# base_schematic.net
KiCad netlist of a schematic drawn in Altium Designer
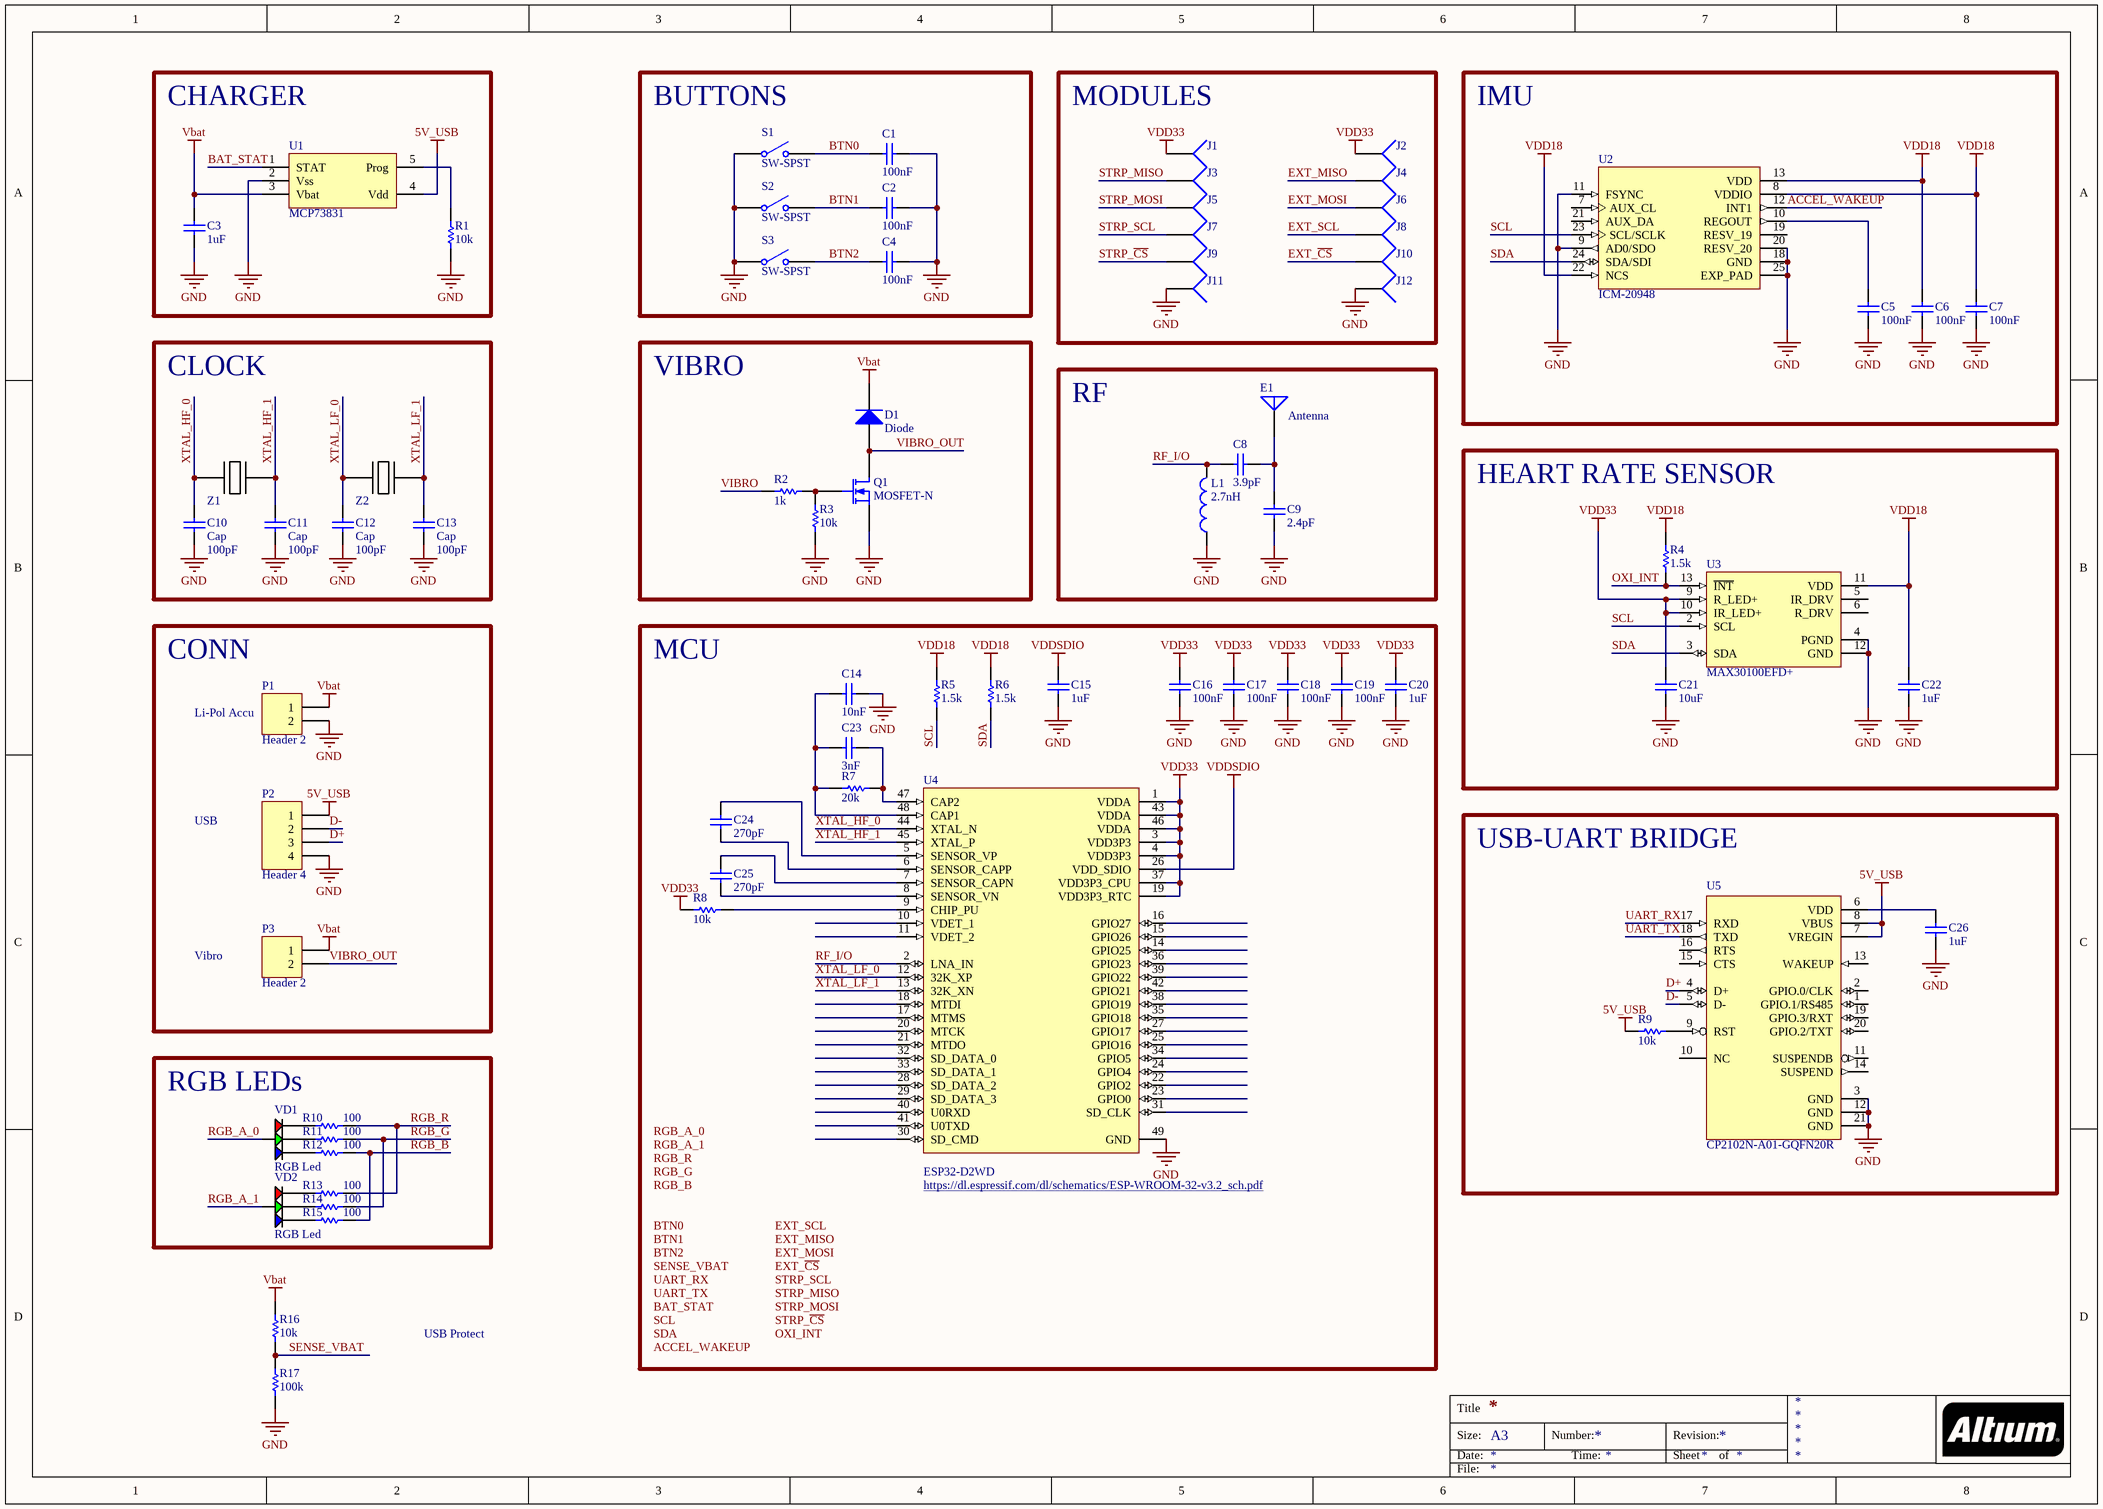
[diagram p0: base_schematic.SchDoc]

(export (version "E")
  (design (tool "Eeschema 10.0.6"))
  (components
    (comp (ref "C1")
      (value "100nF")
      (footprint "RAD-0.3")
      (description "Capacitor")
      (fields (field (name "PUBLISHER") "Altium Limited"))
      (libsource (lib "Miscellaneous Devices") (part "Cap"))
    )
    (comp (ref "C2")
      (value "100nF")
      (footprint "RAD-0.3")
      (description "Capacitor")
      (fields (field (name "PUBLISHER") "Altium Limited"))
      (libsource (lib "Miscellaneous Devices") (part "Cap"))
    )
    (comp (ref "C3")
      (value "1uF")
      (footprint "RAD-0.3")
      (description "Capacitor")
      (fields (field (name "PUBLISHER") "Altium Limited"))
      (libsource (lib "Miscellaneous Devices") (part "Cap"))
    )
    (comp (ref "C4")
      (value "100nF")
      (footprint "RAD-0.3")
      (description "Capacitor")
      (fields (field (name "PUBLISHER") "Altium Limited"))
      (libsource (lib "Miscellaneous Devices") (part "Cap"))
    )
    (comp (ref "C5")
      (value "100nF")
      (footprint "RAD-0.3")
      (description "Capacitor")
      (fields (field (name "PUBLISHER") "Altium Limited"))
      (libsource (lib "Miscellaneous Devices") (part "Cap"))
    )
    (comp (ref "C6")
      (value "100nF")
      (footprint "RAD-0.3")
      (description "Capacitor")
      (fields (field (name "PUBLISHER") "Altium Limited"))
      (libsource (lib "Miscellaneous Devices") (part "Cap"))
    )
    (comp (ref "C7")
      (value "100nF")
      (footprint "RAD-0.3")
      (description "Capacitor")
      (fields (field (name "PUBLISHER") "Altium Limited"))
      (libsource (lib "Miscellaneous Devices") (part "Cap"))
    )
    (comp (ref "C8")
      (value "3.9pF")
      (footprint "RAD-0.3")
      (description "Capacitor")
      (fields (field (name "PUBLISHER") "Altium Limited"))
      (libsource (lib "Miscellaneous Devices") (part "Cap"))
    )
    (comp (ref "C9")
      (value "2.4pF")
      (footprint "RAD-0.3")
      (description "Capacitor")
      (fields (field (name "PUBLISHER") "Altium Limited"))
      (libsource (lib "Miscellaneous Devices") (part "Cap"))
    )
    (comp (ref "C10")
      (value "Cap")
      (footprint "RAD-0.3")
      (description "Capacitor")
      (fields (field (name "ALTIUM_VALUE") "100pF") (field (name "PUBLISHER") "Altium Limited"))
      (libsource (lib "Miscellaneous Devices") (part "Cap"))
    )
    (comp (ref "C11")
      (value "Cap")
      (footprint "RAD-0.3")
      (description "Capacitor")
      (fields (field (name "ALTIUM_VALUE") "100pF") (field (name "PUBLISHER") "Altium Limited"))
      (libsource (lib "Miscellaneous Devices") (part "Cap"))
    )
    (comp (ref "C12")
      (value "Cap")
      (footprint "RAD-0.3")
      (description "Capacitor")
      (fields (field (name "ALTIUM_VALUE") "100pF") (field (name "PUBLISHER") "Altium Limited"))
      (libsource (lib "Miscellaneous Devices") (part "Cap"))
    )
    (comp (ref "C13")
      (value "Cap")
      (footprint "RAD-0.3")
      (description "Capacitor")
      (fields (field (name "ALTIUM_VALUE") "100pF") (field (name "PUBLISHER") "Altium Limited"))
      (libsource (lib "Miscellaneous Devices") (part "Cap"))
    )
    (comp (ref "C14")
      (value "10nF")
      (footprint "RAD-0.3")
      (description "Capacitor")
      (fields (field (name "PUBLISHER") "Altium Limited"))
      (libsource (lib "Miscellaneous Devices") (part "Cap"))
    )
    (comp (ref "C15")
      (value "1uF")
      (footprint "RAD-0.3")
      (description "Capacitor")
      (fields (field (name "PUBLISHER") "Altium Limited"))
      (libsource (lib "Miscellaneous Devices") (part "Cap"))
    )
    (comp (ref "C16")
      (value "100nF")
      (footprint "RAD-0.3")
      (description "Capacitor")
      (fields (field (name "PUBLISHER") "Altium Limited"))
      (libsource (lib "Miscellaneous Devices") (part "Cap"))
    )
    (comp (ref "C17")
      (value "100nF")
      (footprint "RAD-0.3")
      (description "Capacitor")
      (fields (field (name "PUBLISHER") "Altium Limited"))
      (libsource (lib "Miscellaneous Devices") (part "Cap"))
    )
    (comp (ref "C18")
      (value "100nF")
      (footprint "RAD-0.3")
      (description "Capacitor")
      (fields (field (name "PUBLISHER") "Altium Limited"))
      (libsource (lib "Miscellaneous Devices") (part "Cap"))
    )
    (comp (ref "C19")
      (value "100nF")
      (footprint "RAD-0.3")
      (description "Capacitor")
      (fields (field (name "PUBLISHER") "Altium Limited"))
      (libsource (lib "Miscellaneous Devices") (part "Cap"))
    )
    (comp (ref "C20")
      (value "1uF")
      (footprint "RAD-0.3")
      (description "Capacitor")
      (fields (field (name "PUBLISHER") "Altium Limited"))
      (libsource (lib "Miscellaneous Devices") (part "Cap"))
    )
    (comp (ref "C21")
      (value "10uF")
      (footprint "RAD-0.3")
      (description "Capacitor")
      (fields (field (name "PUBLISHER") "Altium Limited"))
      (libsource (lib "Miscellaneous Devices") (part "Cap"))
    )
    (comp (ref "C22")
      (value "1uF")
      (footprint "RAD-0.3")
      (description "Capacitor")
      (fields (field (name "PUBLISHER") "Altium Limited"))
      (libsource (lib "Miscellaneous Devices") (part "Cap"))
    )
    (comp (ref "C23")
      (value "3nF")
      (footprint "RAD-0.3")
      (description "Capacitor")
      (fields (field (name "PUBLISHER") "Altium Limited"))
      (libsource (lib "Miscellaneous Devices") (part "Cap"))
    )
    (comp (ref "C24")
      (value "270pF")
      (footprint "RAD-0.3")
      (description "Capacitor")
      (fields (field (name "PUBLISHER") "Altium Limited"))
      (libsource (lib "Miscellaneous Devices") (part "Cap"))
    )
    (comp (ref "C25")
      (value "270pF")
      (footprint "RAD-0.3")
      (description "Capacitor")
      (fields (field (name "PUBLISHER") "Altium Limited"))
      (libsource (lib "Miscellaneous Devices") (part "Cap"))
    )
    (comp (ref "C26")
      (value "1uF")
      (footprint "RAD-0.3")
      (description "Capacitor")
      (fields (field (name "PUBLISHER") "Altium Limited"))
      (libsource (lib "Miscellaneous Devices") (part "Cap"))
    )
    (comp (ref "D1")
      (value "Diode")
      (footprint "SMC")
      (description "Default Diode")
      (fields (field (name "PUBLISHER") "Altium Limited"))
      (libsource (lib "Miscellaneous Devices") (part "Diode"))
    )
    (comp (ref "E1")
      (value "Antenna")
      (footprint "PIN1")
      (description "Generic Antenna")
      (fields (field (name "PUBLISHER") "Altium Limited"))
      (libsource (lib "Miscellaneous Devices") (part "Antenna"))
    )
    (comp (ref "J1")
      (value "Socket")
      (footprint "PIN1")
      (fields (field (name "PUBLISHER") "Altium Limited"))
      (libsource (lib "Miscellaneous Connectors") (part "Socket"))
    )
    (comp (ref "J2")
      (value "Socket")
      (footprint "PIN1")
      (fields (field (name "PUBLISHER") "Altium Limited"))
      (libsource (lib "Miscellaneous Connectors") (part "Socket"))
    )
    (comp (ref "J3")
      (value "Socket")
      (footprint "PIN1")
      (fields (field (name "PUBLISHER") "Altium Limited"))
      (libsource (lib "Miscellaneous Connectors") (part "Socket"))
    )
    (comp (ref "J4")
      (value "Socket")
      (footprint "PIN1")
      (fields (field (name "PUBLISHER") "Altium Limited"))
      (libsource (lib "Miscellaneous Connectors") (part "Socket"))
    )
    (comp (ref "J5")
      (value "Socket")
      (footprint "PIN1")
      (fields (field (name "PUBLISHER") "Altium Limited"))
      (libsource (lib "Miscellaneous Connectors") (part "Socket"))
    )
    (comp (ref "J6")
      (value "Socket")
      (footprint "PIN1")
      (fields (field (name "PUBLISHER") "Altium Limited"))
      (libsource (lib "Miscellaneous Connectors") (part "Socket"))
    )
    (comp (ref "J7")
      (value "Socket")
      (footprint "PIN1")
      (fields (field (name "PUBLISHER") "Altium Limited"))
      (libsource (lib "Miscellaneous Connectors") (part "Socket"))
    )
    (comp (ref "J8")
      (value "Socket")
      (footprint "PIN1")
      (fields (field (name "PUBLISHER") "Altium Limited"))
      (libsource (lib "Miscellaneous Connectors") (part "Socket"))
    )
    (comp (ref "J9")
      (value "Socket")
      (footprint "PIN1")
      (fields (field (name "PUBLISHER") "Altium Limited"))
      (libsource (lib "Miscellaneous Connectors") (part "Socket"))
    )
    (comp (ref "J10")
      (value "Socket")
      (footprint "PIN1")
      (fields (field (name "PUBLISHER") "Altium Limited"))
      (libsource (lib "Miscellaneous Connectors") (part "Socket"))
    )
    (comp (ref "J11")
      (value "Socket")
      (footprint "PIN1")
      (fields (field (name "PUBLISHER") "Altium Limited"))
      (libsource (lib "Miscellaneous Connectors") (part "Socket"))
    )
    (comp (ref "J12")
      (value "Socket")
      (footprint "PIN1")
      (fields (field (name "PUBLISHER") "Altium Limited"))
      (libsource (lib "Miscellaneous Connectors") (part "Socket"))
    )
    (comp (ref "L1")
      (value "2.7nH")
      (footprint "0402-A")
      (description "Inductor")
      (fields (field (name "PUBLISHER") "Altium Limited"))
      (libsource (lib "Miscellaneous Devices") (part "Inductor"))
    )
    (comp (ref "P1")
      (value "Header 2")
      (footprint "HDR1X2")
      (description "Header, 2-Pin")
      (fields (field (name "PUBLISHER") "Altium Limited"))
      (libsource (lib "Miscellaneous Connectors") (part "Header 2"))
    )
    (comp (ref "P2")
      (value "Header 4")
      (footprint "HDR1X4")
      (description "Header, 4-Pin")
      (fields (field (name "PUBLISHER") "Altium Limited"))
      (libsource (lib "Miscellaneous Connectors") (part "Header 4"))
    )
    (comp (ref "P3")
      (value "Header 2")
      (footprint "HDR1X2")
      (description "Header, 2-Pin")
      (fields (field (name "PUBLISHER") "Altium Limited"))
      (libsource (lib "Miscellaneous Connectors") (part "Header 2"))
    )
    (comp (ref "Q1")
      (value "MOSFET-N")
      (footprint "E3")
      (description "N-Channel MOSFET")
      (fields (field (name "PUBLISHER") "Altium Limited"))
      (libsource (lib "Miscellaneous Devices") (part "MOSFET-N"))
    )
    (comp (ref "R1")
      (value "10k")
      (footprint "AXIAL-0.3")
      (description "Resistor")
      (fields (field (name "PUBLISHER") "Altium Limited"))
      (libsource (lib "Miscellaneous Devices") (part "Res1"))
    )
    (comp (ref "R2")
      (value "1k")
      (footprint "AXIAL-0.3")
      (description "Resistor")
      (fields (field (name "PUBLISHER") "Altium Limited"))
      (libsource (lib "Miscellaneous Devices") (part "Res1"))
    )
    (comp (ref "R3")
      (value "10k")
      (footprint "AXIAL-0.3")
      (description "Resistor")
      (fields (field (name "PUBLISHER") "Altium Limited"))
      (libsource (lib "Miscellaneous Devices") (part "Res1"))
    )
    (comp (ref "R4")
      (value "1.5k")
      (footprint "AXIAL-0.3")
      (description "Resistor")
      (fields (field (name "PUBLISHER") "Altium Limited"))
      (libsource (lib "Miscellaneous Devices") (part "Res1"))
    )
    (comp (ref "R5")
      (value "1.5k")
      (footprint "AXIAL-0.3")
      (description "Resistor")
      (fields (field (name "PUBLISHER") "Altium Limited"))
      (libsource (lib "Miscellaneous Devices") (part "Res1"))
    )
    (comp (ref "R6")
      (value "1.5k")
      (footprint "AXIAL-0.3")
      (description "Resistor")
      (fields (field (name "PUBLISHER") "Altium Limited"))
      (libsource (lib "Miscellaneous Devices") (part "Res1"))
    )
    (comp (ref "R7")
      (value "20k")
      (footprint "AXIAL-0.3")
      (description "Resistor")
      (fields (field (name "PUBLISHER") "Altium Limited"))
      (libsource (lib "Miscellaneous Devices") (part "Res1"))
    )
    (comp (ref "R8")
      (value "10k")
      (footprint "AXIAL-0.3")
      (description "Resistor")
      (fields (field (name "PUBLISHER") "Altium Limited"))
      (libsource (lib "Miscellaneous Devices") (part "Res1"))
    )
    (comp (ref "R9")
      (value "10k")
      (footprint "AXIAL-0.3")
      (description "Resistor")
      (fields (field (name "PUBLISHER") "Altium Limited"))
      (libsource (lib "Miscellaneous Devices") (part "Res1"))
    )
    (comp (ref "R10")
      (value "100")
      (footprint "AXIAL-0.3")
      (description "Resistor")
      (fields (field (name "PUBLISHER") "Altium Limited"))
      (libsource (lib "Miscellaneous Devices") (part "Res1"))
    )
    (comp (ref "R11")
      (value "100")
      (footprint "AXIAL-0.3")
      (description "Resistor")
      (fields (field (name "PUBLISHER") "Altium Limited"))
      (libsource (lib "Miscellaneous Devices") (part "Res1"))
    )
    (comp (ref "R12")
      (value "100")
      (footprint "AXIAL-0.3")
      (description "Resistor")
      (fields (field (name "PUBLISHER") "Altium Limited"))
      (libsource (lib "Miscellaneous Devices") (part "Res1"))
    )
    (comp (ref "R13")
      (value "100")
      (footprint "AXIAL-0.3")
      (description "Resistor")
      (fields (field (name "PUBLISHER") "Altium Limited"))
      (libsource (lib "Miscellaneous Devices") (part "Res1"))
    )
    (comp (ref "R14")
      (value "100")
      (footprint "AXIAL-0.3")
      (description "Resistor")
      (fields (field (name "PUBLISHER") "Altium Limited"))
      (libsource (lib "Miscellaneous Devices") (part "Res1"))
    )
    (comp (ref "R15")
      (value "100")
      (footprint "AXIAL-0.3")
      (description "Resistor")
      (fields (field (name "PUBLISHER") "Altium Limited"))
      (libsource (lib "Miscellaneous Devices") (part "Res1"))
    )
    (comp (ref "R16")
      (value "10k")
      (footprint "AXIAL-0.3")
      (description "Resistor")
      (fields (field (name "PUBLISHER") "Altium Limited"))
      (libsource (lib "Miscellaneous Devices") (part "Res1"))
    )
    (comp (ref "R17")
      (value "100k")
      (footprint "AXIAL-0.3")
      (description "Resistor")
      (fields (field (name "PUBLISHER") "Altium Limited"))
      (libsource (lib "Miscellaneous Devices") (part "Res1"))
    )
    (comp (ref "S1")
      (value "SW-SPST")
      (footprint "SPST-2")
      (description "Single-Pole, Single-Throw Switch")
      (fields (field (name "PUBLISHER") "Altium Limited"))
      (libsource (lib "Miscellaneous Devices") (part "SW-SPST"))
    )
    (comp (ref "S2")
      (value "SW-SPST")
      (footprint "SPST-2")
      (description "Single-Pole, Single-Throw Switch")
      (fields (field (name "PUBLISHER") "Altium Limited"))
      (libsource (lib "Miscellaneous Devices") (part "SW-SPST"))
    )
    (comp (ref "S3")
      (value "SW-SPST")
      (footprint "SPST-2")
      (description "Single-Pole, Single-Throw Switch")
      (fields (field (name "PUBLISHER") "Altium Limited"))
      (libsource (lib "Miscellaneous Devices") (part "SW-SPST"))
    )
    (comp (ref "U1") (value "MCP73831") (footprint "SOT23-5") (libsource (lib "sch_lib") (part "MCP73831")))
    (comp (ref "U2")
      (value "ICM-20948")
      (footprint "QFN40P300X300X105-25N")
      (description "9 Axis=3 Axis Gyro+3 Axis Accel+Compass. Pin For Pin With m")
      (fields (field (name "MF") "TDK InvenSense"))
      (libsource (lib "ICM-20948") (part "ICM-20948"))
    )
    (comp (ref "U3")
      (value "MAX30100EFD+")
      (footprint "LGA14R80P2X7_560X280X130")
      (description "Pulse Oximeter and Heart-Rate Sensor IC 14-Pin OLGA T/R")
      (fields (field (name "MF") "Maxim Integrated") (field (name "MP") "MAX30100EFD+T"))
      (libsource (lib "MAX30100EFD_") (part "MAX30100EFD+"))
    )
    (comp (ref "U4")
      (value "ESP32-D2WD")
      (footprint "QFN35P500X500X90-49N")
      (description "Smd Ic Esp32-D2wd, Dual Core Mcu")
      (fields (field (name "MF") "Espressif Systems"))
      (libsource (lib "sch_lib") (part "ESP32-D2WD"))
    )
    (comp (ref "U5")
      (value "CP2102N-A01-GQFN20R")
      (footprint "SILABS_QFN20")
      (description "Ic Bridge Usb To Uart 20qfn")
      (fields (field (name "MF") "Silicon Labs"))
      (libsource (lib "sch_lib") (part "CP2102N-A01-GQFN20R"))
    )
    (comp (ref "VD1") (value "RGB Led") (libsource (lib "sch_lib") (part "RGB Led")))
    (comp (ref "VD2") (value "RGB Led") (libsource (lib "sch_lib") (part "RGB Led")))
    (comp (ref "Z1")
      (value "~")
      (footprint "RR_CRYSTAL_3.2X1.3")
      (libsource (lib "sch_lib") (part "Crystal_smd"))
    )
    (comp (ref "Z2")
      (value "~")
      (footprint "RR_CRYSTAL_3.2X1.3")
      (libsource (lib "sch_lib") (part "Crystal_smd"))
    )
  )
  (nets
    (net (code "1") (name "/ACCEL_WAKEUP") (class "Default")
      (node (ref "U2") (pin "12") (pinfunction "INT1_12") (pintype "output"))
    )
    (net (code "2") (name "/BAT_STAT") (class "Default")
      (node (ref "U1") (pin "1") (pinfunction "STAT_1") (pintype "passive"))
    )
    (net (code "3") (name "/BTN0") (class "Default")
      (node (ref "C1") (pin "2") (pinfunction "2_2") (pintype "passive"))
      (node (ref "S1") (pin "2") (pinfunction "NO_2") (pintype "passive"))
    )
    (net (code "4") (name "/BTN1") (class "Default")
      (node (ref "C2") (pin "2") (pinfunction "2_2") (pintype "passive"))
      (node (ref "S2") (pin "2") (pinfunction "NO_2") (pintype "passive"))
    )
    (net (code "5") (name "/BTN2") (class "Default")
      (node (ref "C4") (pin "2") (pinfunction "2_2") (pintype "passive"))
      (node (ref "S3") (pin "2") (pinfunction "NO_2") (pintype "passive"))
    )
    (net (code "6") (name "/D+") (class "Default")
      (node (ref "P2") (pin "3") (pinfunction "3_3") (pintype "passive"))
      (node (ref "U5") (pin "4") (pinfunction "D+_4") (pintype "bidirectional"))
    )
    (net (code "7") (name "/D-") (class "Default")
      (node (ref "P2") (pin "2") (pinfunction "2_2") (pintype "passive"))
      (node (ref "U5") (pin "5") (pinfunction "D-_5") (pintype "bidirectional"))
    )
    (net (code "8") (name "/EXT_MISO") (class "Default")
      (node (ref "J4") (pin "1") (pinfunction "1_1") (pintype "passive"))
    )
    (net (code "9") (name "/EXT_MOSI") (class "Default")
      (node (ref "J6") (pin "1") (pinfunction "1_1") (pintype "passive"))
    )
    (net (code "10") (name "/EXT_SCL") (class "Default")
      (node (ref "J8") (pin "1") (pinfunction "1_1") (pintype "passive"))
    )
    (net (code "11") (name "/EXT_~{CS}") (class "Default")
      (node (ref "J10") (pin "1") (pinfunction "1_1") (pintype "passive"))
    )
    (net (code "12") (name "/OXI_INT") (class "Default")
      (node (ref "R4") (pin "1") (pinfunction "1_1") (pintype "passive"))
      (node (ref "U3") (pin "13") (pinfunction "~{INT}_13") (pintype "input"))
    )
    (net (code "13") (name "/RF_I{slash}O") (class "Default")
      (node (ref "C8") (pin "2") (pinfunction "2_2") (pintype "passive"))
      (node (ref "L1") (pin "2") (pinfunction "2_2") (pintype "passive"))
      (node (ref "U4") (pin "2") (pinfunction "LNA_IN_2") (pintype "bidirectional"))
    )
    (net (code "14") (name "/RGB_A_0") (class "Default")
      (node (ref "VD1") (pin "2") (pinfunction "C_2") (pintype "passive"))
    )
    (net (code "15") (name "/RGB_A_1") (class "Default")
      (node (ref "VD2") (pin "2") (pinfunction "C_2") (pintype "passive"))
    )
    (net (code "16") (name "/RGB_B") (class "Default")
      (node (ref "R12") (pin "2") (pinfunction "2_2") (pintype "passive"))
      (node (ref "R15") (pin "2") (pinfunction "2_2") (pintype "passive"))
    )
    (net (code "17") (name "/RGB_G") (class "Default")
      (node (ref "R11") (pin "2") (pinfunction "2_2") (pintype "passive"))
      (node (ref "R14") (pin "2") (pinfunction "2_2") (pintype "passive"))
    )
    (net (code "18") (name "/RGB_R") (class "Default")
      (node (ref "R10") (pin "2") (pinfunction "2_2") (pintype "passive"))
      (node (ref "R13") (pin "2") (pinfunction "2_2") (pintype "passive"))
    )
    (net (code "19") (name "/SCL") (class "Default")
      (node (ref "R5") (pin "1") (pinfunction "1_1") (pintype "passive"))
      (node (ref "U2") (pin "23") (pinfunction "SCL/SCLK_23") (pintype "input"))
      (node (ref "U3") (pin "2") (pinfunction "SCL_2") (pintype "input"))
    )
    (net (code "20") (name "/SDA") (class "Default")
      (node (ref "R6") (pin "1") (pinfunction "1_1") (pintype "passive"))
      (node (ref "U2") (pin "24") (pinfunction "SDA/SDI_24") (pintype "bidirectional"))
      (node (ref "U3") (pin "3") (pinfunction "SDA_3") (pintype "bidirectional"))
    )
    (net (code "21") (name "/SENSE_VBAT") (class "Default")
      (node (ref "R16") (pin "1") (pinfunction "1_1") (pintype "passive"))
      (node (ref "R17") (pin "2") (pinfunction "2_2") (pintype "passive"))
    )
    (net (code "22") (name "/STRP_MISO") (class "Default")
      (node (ref "J3") (pin "1") (pinfunction "1_1") (pintype "passive"))
    )
    (net (code "23") (name "/STRP_MOSI") (class "Default")
      (node (ref "J5") (pin "1") (pinfunction "1_1") (pintype "passive"))
    )
    (net (code "24") (name "/STRP_SCL") (class "Default")
      (node (ref "J7") (pin "1") (pinfunction "1_1") (pintype "passive"))
    )
    (net (code "25") (name "/STRP_~{CS}") (class "Default")
      (node (ref "J9") (pin "1") (pinfunction "1_1") (pintype "passive"))
    )
    (net (code "26") (name "/UART_RX") (class "Default")
      (node (ref "U5") (pin "17") (pinfunction "RXD_17") (pintype "input"))
    )
    (net (code "27") (name "/UART_TX") (class "Default")
      (node (ref "U5") (pin "18") (pinfunction "TXD_18") (pintype "output"))
    )
    (net (code "28") (name "/VIBRO") (class "Default")
      (node (ref "R2") (pin "1") (pinfunction "1_1") (pintype "passive"))
    )
    (net (code "29") (name "/VIBRO_OUT") (class "Default")
      (node (ref "D1") (pin "1") (pinfunction "A_1") (pintype "passive"))
      (node (ref "P3") (pin "2") (pinfunction "2_2") (pintype "passive"))
      (node (ref "Q1") (pin "1") (pinfunction "D_1") (pintype "passive"))
    )
    (net (code "30") (name "/XTAL_HF_0") (class "Default")
      (node (ref "C10") (pin "2") (pinfunction "2_2") (pintype "passive"))
      (node (ref "U4") (pin "44") (pinfunction "XTAL_N_44") (pintype "input"))
      (node (ref "Z1") (pin "1") (pinfunction "X1_1") (pintype "passive"))
    )
    (net (code "31") (name "/XTAL_HF_1") (class "Default")
      (node (ref "C11") (pin "2") (pinfunction "2_2") (pintype "passive"))
      (node (ref "U4") (pin "45") (pinfunction "XTAL_P_45") (pintype "input"))
      (node (ref "Z1") (pin "3") (pinfunction "X2_3") (pintype "passive"))
    )
    (net (code "32") (name "/XTAL_LF_0") (class "Default")
      (node (ref "C12") (pin "2") (pinfunction "2_2") (pintype "passive"))
      (node (ref "U4") (pin "12") (pinfunction "32K_XP_12") (pintype "bidirectional"))
      (node (ref "Z2") (pin "1") (pinfunction "X1_1") (pintype "passive"))
    )
    (net (code "33") (name "/XTAL_LF_1") (class "Default")
      (node (ref "C13") (pin "2") (pinfunction "2_2") (pintype "passive"))
      (node (ref "U4") (pin "13") (pinfunction "32K_XN_13") (pintype "bidirectional"))
      (node (ref "Z2") (pin "3") (pinfunction "X2_3") (pintype "passive"))
    )
    (net (code "34") (name "5V_USB") (class "Default")
      (node (ref "P2") (pin "1") (pinfunction "1_1") (pintype "passive"))
      (node (ref "R9") (pin "2") (pinfunction "2_2") (pintype "passive"))
      (node (ref "U1") (pin "4") (pinfunction "Vdd_4") (pintype "passive"))
      (node (ref "U5") (pin "7") (pinfunction "VREGIN_7") (pintype "power_in"))
      (node (ref "U5") (pin "8") (pinfunction "VBUS_8") (pintype "power_in"))
    )
    (net (code "35") (name "GND") (class "Default")
      (node (ref "C1") (pin "1") (pinfunction "1_1") (pintype "passive"))
      (node (ref "C10") (pin "1") (pinfunction "1_1") (pintype "passive"))
      (node (ref "C11") (pin "1") (pinfunction "1_1") (pintype "passive"))
      (node (ref "C12") (pin "1") (pinfunction "1_1") (pintype "passive"))
      (node (ref "C13") (pin "1") (pinfunction "1_1") (pintype "passive"))
      (node (ref "C14") (pin "2") (pinfunction "2_2") (pintype "passive"))
      (node (ref "C15") (pin "1") (pinfunction "1_1") (pintype "passive"))
      (node (ref "C16") (pin "1") (pinfunction "1_1") (pintype "passive"))
      (node (ref "C17") (pin "1") (pinfunction "1_1") (pintype "passive"))
      (node (ref "C18") (pin "1") (pinfunction "1_1") (pintype "passive"))
      (node (ref "C19") (pin "1") (pinfunction "1_1") (pintype "passive"))
      (node (ref "C2") (pin "1") (pinfunction "1_1") (pintype "passive"))
      (node (ref "C20") (pin "1") (pinfunction "1_1") (pintype "passive"))
      (node (ref "C21") (pin "1") (pinfunction "1_1") (pintype "passive"))
      (node (ref "C22") (pin "1") (pinfunction "1_1") (pintype "passive"))
      (node (ref "C26") (pin "1") (pinfunction "1_1") (pintype "passive"))
      (node (ref "C3") (pin "1") (pinfunction "1_1") (pintype "passive"))
      (node (ref "C4") (pin "1") (pinfunction "1_1") (pintype "passive"))
      (node (ref "C5") (pin "1") (pinfunction "1_1") (pintype "passive"))
      (node (ref "C6") (pin "1") (pinfunction "1_1") (pintype "passive"))
      (node (ref "C7") (pin "1") (pinfunction "1_1") (pintype "passive"))
      (node (ref "C9") (pin "1") (pinfunction "1_1") (pintype "passive"))
      (node (ref "J11") (pin "1") (pinfunction "1_1") (pintype "passive"))
      (node (ref "J12") (pin "1") (pinfunction "1_1") (pintype "passive"))
      (node (ref "L1") (pin "1") (pinfunction "1_1") (pintype "passive"))
      (node (ref "P1") (pin "2") (pinfunction "2_2") (pintype "passive"))
      (node (ref "P2") (pin "4") (pinfunction "4_4") (pintype "passive"))
      (node (ref "Q1") (pin "3") (pinfunction "S_3") (pintype "passive"))
      (node (ref "R1") (pin "2") (pinfunction "2_2") (pintype "passive"))
      (node (ref "R17") (pin "1") (pinfunction "1_1") (pintype "passive"))
      (node (ref "R3") (pin "1") (pinfunction "1_1") (pintype "passive"))
      (node (ref "S1") (pin "1") (pinfunction "COMMON_1") (pintype "passive"))
      (node (ref "S2") (pin "1") (pinfunction "COMMON_1") (pintype "passive"))
      (node (ref "S3") (pin "1") (pinfunction "COMMON_1") (pintype "passive"))
      (node (ref "U1") (pin "2") (pinfunction "Vss_2") (pintype "passive"))
      (node (ref "U2") (pin "11") (pinfunction "FSYNC_11") (pintype "input"))
      (node (ref "U2") (pin "18") (pinfunction "GND_18") (pintype "power_in"))
      (node (ref "U2") (pin "20") (pinfunction "RESV_20_20") (pintype "passive"))
      (node (ref "U2") (pin "25") (pinfunction "EXP_PAD_25") (pintype "power_in"))
      (node (ref "U2") (pin "9") (pinfunction "AD0/SDO_9") (pintype "output"))
      (node (ref "U3") (pin "12") (pinfunction "GND_12") (pintype "passive"))
      (node (ref "U3") (pin "4") (pinfunction "PGND_4") (pintype "passive"))
      (node (ref "U4") (pin "49") (pinfunction "GND_49") (pintype "power_in"))
      (node (ref "U5") (pin "12") (pinfunction "GND_12") (pintype "power_in"))
      (node (ref "U5") (pin "21") (pinfunction "GND_21") (pintype "power_in"))
      (node (ref "U5") (pin "3") (pinfunction "GND_3") (pintype "power_in"))
    )
    (net (code "36") (name "Net-(E1-A)") (class "Default")
      (node (ref "C8") (pin "1") (pinfunction "1_1") (pintype "passive"))
      (node (ref "C9") (pin "2") (pinfunction "2_2") (pintype "passive"))
      (node (ref "E1") (pin "1") (pinfunction "A_1") (pintype "passive"))
    )
    (net (code "37") (name "Net-(Q1-G)") (class "Default")
      (node (ref "Q1") (pin "2") (pinfunction "G_2") (pintype "passive"))
      (node (ref "R2") (pin "2") (pinfunction "2_2") (pintype "passive"))
      (node (ref "R3") (pin "2") (pinfunction "2_2") (pintype "passive"))
    )
    (net (code "38") (name "Net-(U1-Prog)") (class "Default")
      (node (ref "R1") (pin "1") (pinfunction "1_1") (pintype "passive"))
      (node (ref "U1") (pin "5") (pinfunction "Prog_5") (pintype "passive"))
    )
    (net (code "39") (name "Net-(U2-REGOUT)") (class "Default")
      (node (ref "C5") (pin "2") (pinfunction "2_2") (pintype "passive"))
      (node (ref "U2") (pin "10") (pinfunction "REGOUT_10") (pintype "output"))
    )
    (net (code "40") (name "Net-(U4-CAP1)") (class "Default")
      (node (ref "C14") (pin "1") (pinfunction "1_1") (pintype "passive"))
      (node (ref "C23") (pin "1") (pinfunction "1_1") (pintype "passive"))
      (node (ref "R7") (pin "1") (pinfunction "1_1") (pintype "passive"))
      (node (ref "U4") (pin "48") (pinfunction "CAP1_48") (pintype "input"))
    )
    (net (code "41") (name "Net-(U4-CAP2)") (class "Default")
      (node (ref "C23") (pin "2") (pinfunction "2_2") (pintype "passive"))
      (node (ref "R7") (pin "2") (pinfunction "2_2") (pintype "passive"))
      (node (ref "U4") (pin "47") (pinfunction "CAP2_47") (pintype "input"))
    )
    (net (code "42") (name "Net-(U4-CHIP_PU)") (class "Default")
      (node (ref "R8") (pin "2") (pinfunction "2_2") (pintype "passive"))
      (node (ref "U4") (pin "9") (pinfunction "CHIP_PU_9") (pintype "input"))
    )
    (net (code "43") (name "Net-(U4-SENSOR_CAPN)") (class "Default")
      (node (ref "C25") (pin "2") (pinfunction "2_2") (pintype "passive"))
      (node (ref "U4") (pin "7") (pinfunction "SENSOR_CAPN_7") (pintype "input"))
    )
    (net (code "44") (name "Net-(U4-SENSOR_CAPP)") (class "Default")
      (node (ref "C24") (pin "1") (pinfunction "1_1") (pintype "passive"))
      (node (ref "U4") (pin "6") (pinfunction "SENSOR_CAPP_6") (pintype "input"))
    )
    (net (code "45") (name "Net-(U4-SENSOR_VN)") (class "Default")
      (node (ref "C25") (pin "1") (pinfunction "1_1") (pintype "passive"))
      (node (ref "U4") (pin "8") (pinfunction "SENSOR_VN_8") (pintype "input"))
    )
    (net (code "46") (name "Net-(U4-SENSOR_VP)") (class "Default")
      (node (ref "C24") (pin "2") (pinfunction "2_2") (pintype "passive"))
      (node (ref "U4") (pin "5") (pinfunction "SENSOR_VP_5") (pintype "input"))
    )
    (net (code "47") (name "Net-(U5-RST)") (class "Default")
      (node (ref "R9") (pin "1") (pinfunction "1_1") (pintype "passive"))
      (node (ref "U5") (pin "9") (pinfunction "RST_9") (pintype "input"))
    )
    (net (code "48") (name "Net-(U5-VDD)") (class "Default")
      (node (ref "C26") (pin "2") (pinfunction "2_2") (pintype "passive"))
      (node (ref "U5") (pin "6") (pinfunction "VDD_6") (pintype "power_in"))
    )
    (net (code "49") (name "Net-(VD1-B)") (class "Default")
      (node (ref "R12") (pin "1") (pinfunction "1_1") (pintype "passive"))
      (node (ref "VD1") (pin "4") (pinfunction "B_4") (pintype "passive"))
    )
    (net (code "50") (name "Net-(VD1-G)") (class "Default")
      (node (ref "R11") (pin "1") (pinfunction "1_1") (pintype "passive"))
      (node (ref "VD1") (pin "3") (pinfunction "G_3") (pintype "passive"))
    )
    (net (code "51") (name "Net-(VD1-R)") (class "Default")
      (node (ref "R10") (pin "1") (pinfunction "1_1") (pintype "passive"))
      (node (ref "VD1") (pin "1") (pinfunction "R_1") (pintype "passive"))
    )
    (net (code "52") (name "Net-(VD2-B)") (class "Default")
      (node (ref "R15") (pin "1") (pinfunction "1_1") (pintype "passive"))
      (node (ref "VD2") (pin "4") (pinfunction "B_4") (pintype "passive"))
    )
    (net (code "53") (name "Net-(VD2-G)") (class "Default")
      (node (ref "R14") (pin "1") (pinfunction "1_1") (pintype "passive"))
      (node (ref "VD2") (pin "3") (pinfunction "G_3") (pintype "passive"))
    )
    (net (code "54") (name "Net-(VD2-R)") (class "Default")
      (node (ref "R13") (pin "1") (pinfunction "1_1") (pintype "passive"))
      (node (ref "VD2") (pin "1") (pinfunction "R_1") (pintype "passive"))
    )
    (net (code "55") (name "VDD18") (class "Default")
      (node (ref "C22") (pin "2") (pinfunction "2_2") (pintype "passive"))
      (node (ref "C6") (pin "2") (pinfunction "2_2") (pintype "passive"))
      (node (ref "C7") (pin "2") (pinfunction "2_2") (pintype "passive"))
      (node (ref "R4") (pin "2") (pinfunction "2_2") (pintype "passive"))
      (node (ref "R5") (pin "2") (pinfunction "2_2") (pintype "passive"))
      (node (ref "R6") (pin "2") (pinfunction "2_2") (pintype "passive"))
      (node (ref "U2") (pin "13") (pinfunction "VDD_13") (pintype "power_in"))
      (node (ref "U2") (pin "22") (pinfunction "NCS_22") (pintype "input"))
      (node (ref "U2") (pin "8") (pinfunction "VDDIO_8") (pintype "power_in"))
      (node (ref "U3") (pin "11") (pinfunction "VDD_11") (pintype "power_in"))
    )
    (net (code "56") (name "VDD33") (class "Default")
      (node (ref "C16") (pin "2") (pinfunction "2_2") (pintype "passive"))
      (node (ref "C17") (pin "2") (pinfunction "2_2") (pintype "passive"))
      (node (ref "C18") (pin "2") (pinfunction "2_2") (pintype "passive"))
      (node (ref "C19") (pin "2") (pinfunction "2_2") (pintype "passive"))
      (node (ref "C20") (pin "2") (pinfunction "2_2") (pintype "passive"))
      (node (ref "C21") (pin "2") (pinfunction "2_2") (pintype "passive"))
      (node (ref "J1") (pin "1") (pinfunction "1_1") (pintype "passive"))
      (node (ref "J2") (pin "1") (pinfunction "1_1") (pintype "passive"))
      (node (ref "R8") (pin "1") (pinfunction "1_1") (pintype "passive"))
      (node (ref "U3") (pin "10") (pinfunction "IR_LED+_10") (pintype "input"))
      (node (ref "U3") (pin "9") (pinfunction "R_LED+_9") (pintype "input"))
      (node (ref "U4") (pin "1") (pinfunction "VDDA_1") (pintype "power_in"))
      (node (ref "U4") (pin "19") (pinfunction "VDD3P3_RTC_19") (pintype "power_in"))
      (node (ref "U4") (pin "3") (pinfunction "VDD3P3_3") (pintype "power_in"))
      (node (ref "U4") (pin "37") (pinfunction "VDD3P3_CPU_37") (pintype "power_in"))
      (node (ref "U4") (pin "4") (pinfunction "VDD3P3_4") (pintype "power_in"))
      (node (ref "U4") (pin "43") (pinfunction "VDDA_43") (pintype "power_in"))
      (node (ref "U4") (pin "46") (pinfunction "VDDA_46") (pintype "power_in"))
    )
    (net (code "57") (name "VDDSDIO") (class "Default")
      (node (ref "C15") (pin "2") (pinfunction "2_2") (pintype "passive"))
      (node (ref "U4") (pin "26") (pinfunction "VDD_SDIO_26") (pintype "power_in"))
    )
    (net (code "58") (name "Vbat") (class "Default")
      (node (ref "C3") (pin "2") (pinfunction "2_2") (pintype "passive"))
      (node (ref "D1") (pin "2") (pinfunction "K_2") (pintype "passive"))
      (node (ref "P1") (pin "1") (pinfunction "1_1") (pintype "passive"))
      (node (ref "P3") (pin "1") (pinfunction "1_1") (pintype "passive"))
      (node (ref "R16") (pin "2") (pinfunction "2_2") (pintype "passive"))
      (node (ref "U1") (pin "3") (pinfunction "Vbat_3") (pintype "passive"))
    )
    (net (code "59") (name "unconnected-(U2-AUX_CL-Pad7)") (class "Default")
      (node (ref "U2") (pin "7") (pinfunction "AUX_CL_7") (pintype "input"))
    )
    (net (code "60") (name "unconnected-(U2-AUX_DA-Pad21)") (class "Default")
      (node (ref "U2") (pin "21") (pinfunction "AUX_DA_21") (pintype "input"))
    )
    (net (code "61") (name "unconnected-(U2-RESV_19-Pad19)") (class "Default")
      (node (ref "U2") (pin "19") (pinfunction "RESV_19_19") (pintype "passive"))
    )
    (net (code "62") (name "unconnected-(U3-IR_DRV-Pad5)") (class "Default")
      (node (ref "U3") (pin "5") (pinfunction "IR_DRV_5") (pintype "passive"))
    )
    (net (code "63") (name "unconnected-(U3-R_DRV-Pad6)") (class "Default")
      (node (ref "U3") (pin "6") (pinfunction "R_DRV_6") (pintype "passive"))
    )
    (net (code "64") (name "unconnected-(U4-GPIO0-Pad23)") (class "Default")
      (node (ref "U4") (pin "23") (pinfunction "GPIO0_23") (pintype "bidirectional"))
    )
    (net (code "65") (name "unconnected-(U4-GPIO2-Pad22)") (class "Default")
      (node (ref "U4") (pin "22") (pinfunction "GPIO2_22") (pintype "bidirectional"))
    )
    (net (code "66") (name "unconnected-(U4-GPIO4-Pad24)") (class "Default")
      (node (ref "U4") (pin "24") (pinfunction "GPIO4_24") (pintype "bidirectional"))
    )
    (net (code "67") (name "unconnected-(U4-GPIO5-Pad34)") (class "Default")
      (node (ref "U4") (pin "34") (pinfunction "GPIO5_34") (pintype "bidirectional"))
    )
    (net (code "68") (name "unconnected-(U4-GPIO16-Pad25)") (class "Default")
      (node (ref "U4") (pin "25") (pinfunction "GPIO16_25") (pintype "bidirectional"))
    )
    (net (code "69") (name "unconnected-(U4-GPIO17-Pad27)") (class "Default")
      (node (ref "U4") (pin "27") (pinfunction "GPIO17_27") (pintype "bidirectional"))
    )
    (net (code "70") (name "unconnected-(U4-GPIO18-Pad35)") (class "Default")
      (node (ref "U4") (pin "35") (pinfunction "GPIO18_35") (pintype "bidirectional"))
    )
    (net (code "71") (name "unconnected-(U4-GPIO19-Pad38)") (class "Default")
      (node (ref "U4") (pin "38") (pinfunction "GPIO19_38") (pintype "bidirectional"))
    )
    (net (code "72") (name "unconnected-(U4-GPIO21-Pad42)") (class "Default")
      (node (ref "U4") (pin "42") (pinfunction "GPIO21_42") (pintype "bidirectional"))
    )
    (net (code "73") (name "unconnected-(U4-GPIO22-Pad39)") (class "Default")
      (node (ref "U4") (pin "39") (pinfunction "GPIO22_39") (pintype "bidirectional"))
    )
    (net (code "74") (name "unconnected-(U4-GPIO23-Pad36)") (class "Default")
      (node (ref "U4") (pin "36") (pinfunction "GPIO23_36") (pintype "bidirectional"))
    )
    (net (code "75") (name "unconnected-(U4-GPIO25-Pad14)") (class "Default")
      (node (ref "U4") (pin "14") (pinfunction "GPIO25_14") (pintype "bidirectional"))
    )
    (net (code "76") (name "unconnected-(U4-GPIO26-Pad15)") (class "Default")
      (node (ref "U4") (pin "15") (pinfunction "GPIO26_15") (pintype "bidirectional"))
    )
    (net (code "77") (name "unconnected-(U4-GPIO27-Pad16)") (class "Default")
      (node (ref "U4") (pin "16") (pinfunction "GPIO27_16") (pintype "bidirectional"))
    )
    (net (code "78") (name "unconnected-(U4-MTCK-Pad20)") (class "Default")
      (node (ref "U4") (pin "20") (pinfunction "MTCK_20") (pintype "bidirectional"))
    )
    (net (code "79") (name "unconnected-(U4-MTDI-Pad18)") (class "Default")
      (node (ref "U4") (pin "18") (pinfunction "MTDI_18") (pintype "bidirectional"))
    )
    (net (code "80") (name "unconnected-(U4-MTDO-Pad21)") (class "Default")
      (node (ref "U4") (pin "21") (pinfunction "MTDO_21") (pintype "bidirectional"))
    )
    (net (code "81") (name "unconnected-(U4-MTMS-Pad17)") (class "Default")
      (node (ref "U4") (pin "17") (pinfunction "MTMS_17") (pintype "bidirectional"))
    )
    (net (code "82") (name "unconnected-(U4-SD_CLK-Pad31)") (class "Default")
      (node (ref "U4") (pin "31") (pinfunction "SD_CLK_31") (pintype "bidirectional"))
    )
    (net (code "83") (name "unconnected-(U4-SD_CMD-Pad30)") (class "Default")
      (node (ref "U4") (pin "30") (pinfunction "SD_CMD_30") (pintype "bidirectional"))
    )
    (net (code "84") (name "unconnected-(U4-SD_DATA_0-Pad32)") (class "Default")
      (node (ref "U4") (pin "32") (pinfunction "SD_DATA_0_32") (pintype "bidirectional"))
    )
    (net (code "85") (name "unconnected-(U4-SD_DATA_1-Pad33)") (class "Default")
      (node (ref "U4") (pin "33") (pinfunction "SD_DATA_1_33") (pintype "bidirectional"))
    )
    (net (code "86") (name "unconnected-(U4-SD_DATA_2-Pad28)") (class "Default")
      (node (ref "U4") (pin "28") (pinfunction "SD_DATA_2_28") (pintype "bidirectional"))
    )
    (net (code "87") (name "unconnected-(U4-SD_DATA_3-Pad29)") (class "Default")
      (node (ref "U4") (pin "29") (pinfunction "SD_DATA_3_29") (pintype "bidirectional"))
    )
    (net (code "88") (name "unconnected-(U4-U0RXD-Pad40)") (class "Default")
      (node (ref "U4") (pin "40") (pinfunction "U0RXD_40") (pintype "bidirectional"))
    )
    (net (code "89") (name "unconnected-(U4-U0TXD-Pad41)") (class "Default")
      (node (ref "U4") (pin "41") (pinfunction "U0TXD_41") (pintype "bidirectional"))
    )
    (net (code "90") (name "unconnected-(U4-VDET_1-Pad10)") (class "Default")
      (node (ref "U4") (pin "10") (pinfunction "VDET_1_10") (pintype "input"))
    )
    (net (code "91") (name "unconnected-(U4-VDET_2-Pad11)") (class "Default")
      (node (ref "U4") (pin "11") (pinfunction "VDET_2_11") (pintype "input"))
    )
    (net (code "92") (name "unconnected-(U5-CTS-Pad15)") (class "Default")
      (node (ref "U5") (pin "15") (pinfunction "CTS_15") (pintype "input"))
    )
    (net (code "93") (name "unconnected-(U5-GPIO.0{slash}CLK-Pad2)") (class "Default")
      (node (ref "U5") (pin "2") (pinfunction "GPIO.0/CLK_2") (pintype "bidirectional"))
    )
    (net (code "94") (name "unconnected-(U5-GPIO.1{slash}RS485-Pad1)") (class "Default")
      (node (ref "U5") (pin "1") (pinfunction "GPIO.1/RS485_1") (pintype "bidirectional"))
    )
    (net (code "95") (name "unconnected-(U5-GPIO.2{slash}TXT-Pad20)") (class "Default")
      (node (ref "U5") (pin "20") (pinfunction "GPIO.2/TXT_20") (pintype "bidirectional"))
    )
    (net (code "96") (name "unconnected-(U5-GPIO.3{slash}RXT-Pad19)") (class "Default")
      (node (ref "U5") (pin "19") (pinfunction "GPIO.3/RXT_19") (pintype "bidirectional"))
    )
    (net (code "97") (name "unconnected-(U5-NC-Pad10)") (class "Default")
      (node (ref "U5") (pin "10") (pinfunction "NC_10") (pintype "passive"))
    )
    (net (code "98") (name "unconnected-(U5-RTS-Pad16)") (class "Default")
      (node (ref "U5") (pin "16") (pinfunction "RTS_16") (pintype "output"))
    )
    (net (code "99") (name "unconnected-(U5-SUSPEND-Pad14)") (class "Default")
      (node (ref "U5") (pin "14") (pinfunction "SUSPEND_14") (pintype "output"))
    )
    (net (code "100") (name "unconnected-(U5-SUSPENDB-Pad11)") (class "Default")
      (node (ref "U5") (pin "11") (pinfunction "SUSPENDB_11") (pintype "output"))
    )
    (net (code "101") (name "unconnected-(U5-WAKEUP-Pad13)") (class "Default")
      (node (ref "U5") (pin "13") (pinfunction "WAKEUP_13") (pintype "input"))
    )
  )
)
